# CCM_0016.net
KiCad netlist of a schematic drawn in EAGLE
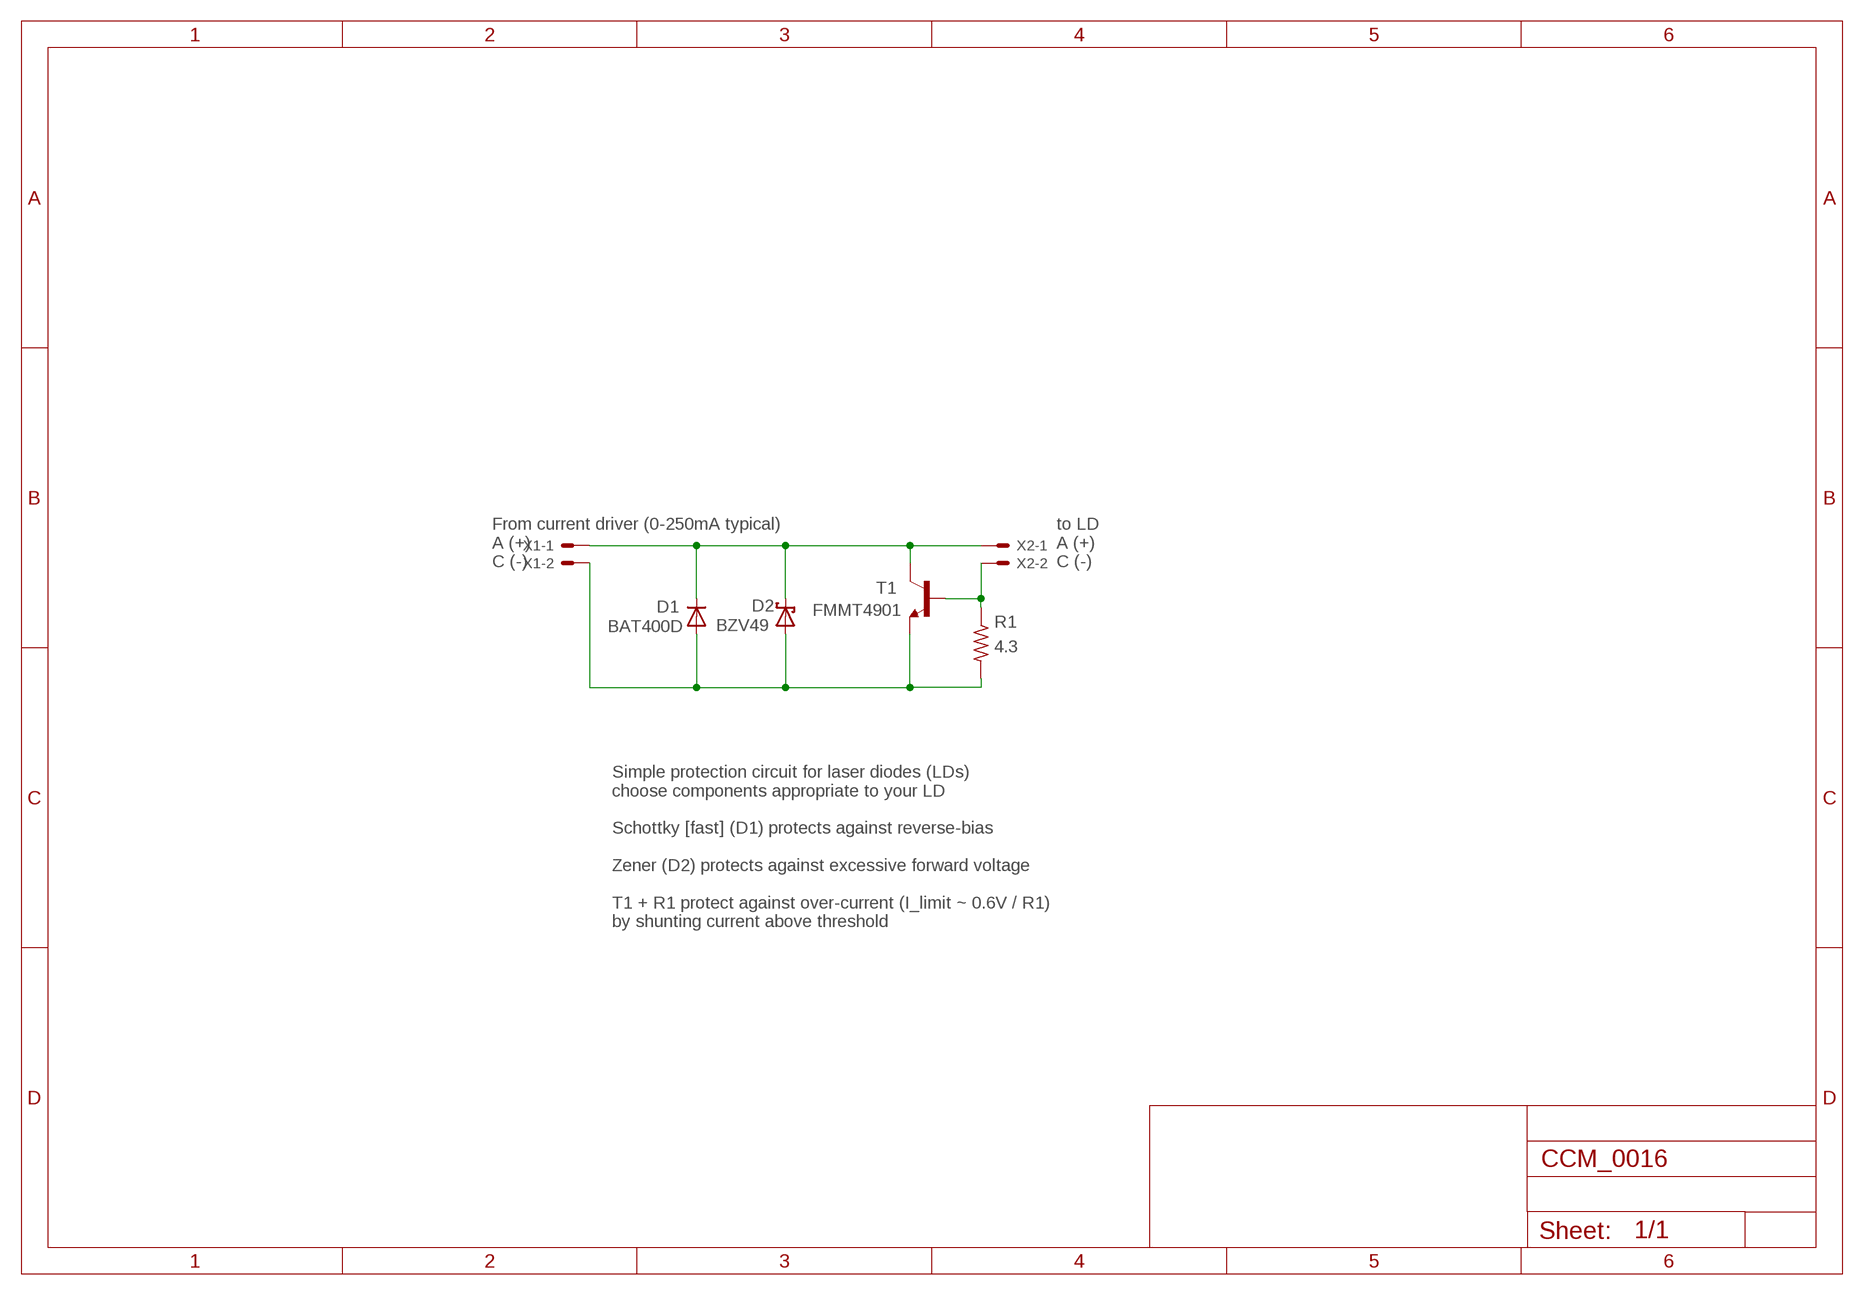
[diagram p0: schematic, sheet 1]

(export (version "E")
  (design (tool "Eeschema 10.0.6"))
  (components
    (comp (ref "D1")
      (value "BAT400D")
      (footprint "eagle-import:SOT23")
      (libsource (lib "eagle-import") (part "HSMS-2850"))
    )
    (comp (ref "D2")
      (value "BZV49")
      (footprint "eagle-import:SOT89")
      (libsource (lib "eagle-import") (part "BZV49"))
    )
    (comp (ref "R1")
      (value "4.3")
      (footprint "eagle-import:2512")
      (libsource (lib "eagle-import") (part "RESISTOR2512"))
    )
    (comp (ref "T1")
      (value "FMMT4901")
      (footprint "eagle-import:SOT23-BEC")
      (libsource (lib "eagle-import") (part "-NPN-SOT23-BECMMBT4401LT1"))
    )
    (comp (ref "X1")
      (value "22-23-2021")
      (footprint "eagle-import:22-23-2021")
      (fields (field (name "MF") "MOLEX"))
      (libsource (lib "eagle-import") (part "22-23-2021"))
    )
    (comp (ref "X2")
      (value "22-23-2021")
      (footprint "eagle-import:22-23-2021")
      (fields (field (name "MF") "MOLEX"))
      (libsource (lib "eagle-import") (part "22-23-2021"))
    )
  )
  (nets
    (net (code "1") (name "Net-(D1-A)") (class "Default")
      (node (ref "D1") (pin "1") (pinfunction "A_1") (pintype "passive"))
      (node (ref "D2") (pin "1") (pinfunction "A_1") (pintype "passive"))
      (node (ref "D2") (pin "3") (pinfunction "A_3") (pintype "passive"))
      (node (ref "R1") (pin "2") (pinfunction "2_2") (pintype "passive"))
      (node (ref "T1") (pin "E") (pinfunction "E_E") (pintype "passive"))
      (node (ref "X1") (pin "2") (pinfunction "S_2") (pintype "passive"))
    )
    (net (code "2") (name "Net-(D1-C)") (class "Default")
      (node (ref "D1") (pin "3") (pinfunction "C_3") (pintype "passive"))
      (node (ref "D2") (pin "2") (pinfunction "C_2") (pintype "passive"))
      (node (ref "D2") (pin "2@1") (pinfunction "C_2@1") (pintype "passive"))
      (node (ref "T1") (pin "C") (pinfunction "C_C") (pintype "passive"))
      (node (ref "X1") (pin "1") (pinfunction "S_1") (pintype "passive"))
      (node (ref "X2") (pin "1") (pinfunction "S_1") (pintype "passive"))
    )
    (net (code "3") (name "Net-(X2B-S)") (class "Default")
      (node (ref "R1") (pin "1") (pinfunction "1_1") (pintype "passive"))
      (node (ref "T1") (pin "B") (pinfunction "B_B") (pintype "passive"))
      (node (ref "X2") (pin "2") (pinfunction "S_2") (pintype "passive"))
    )
  )
)
